# ButtonsLEDs.net
KiCad netlist of a schematic drawn in EAGLE
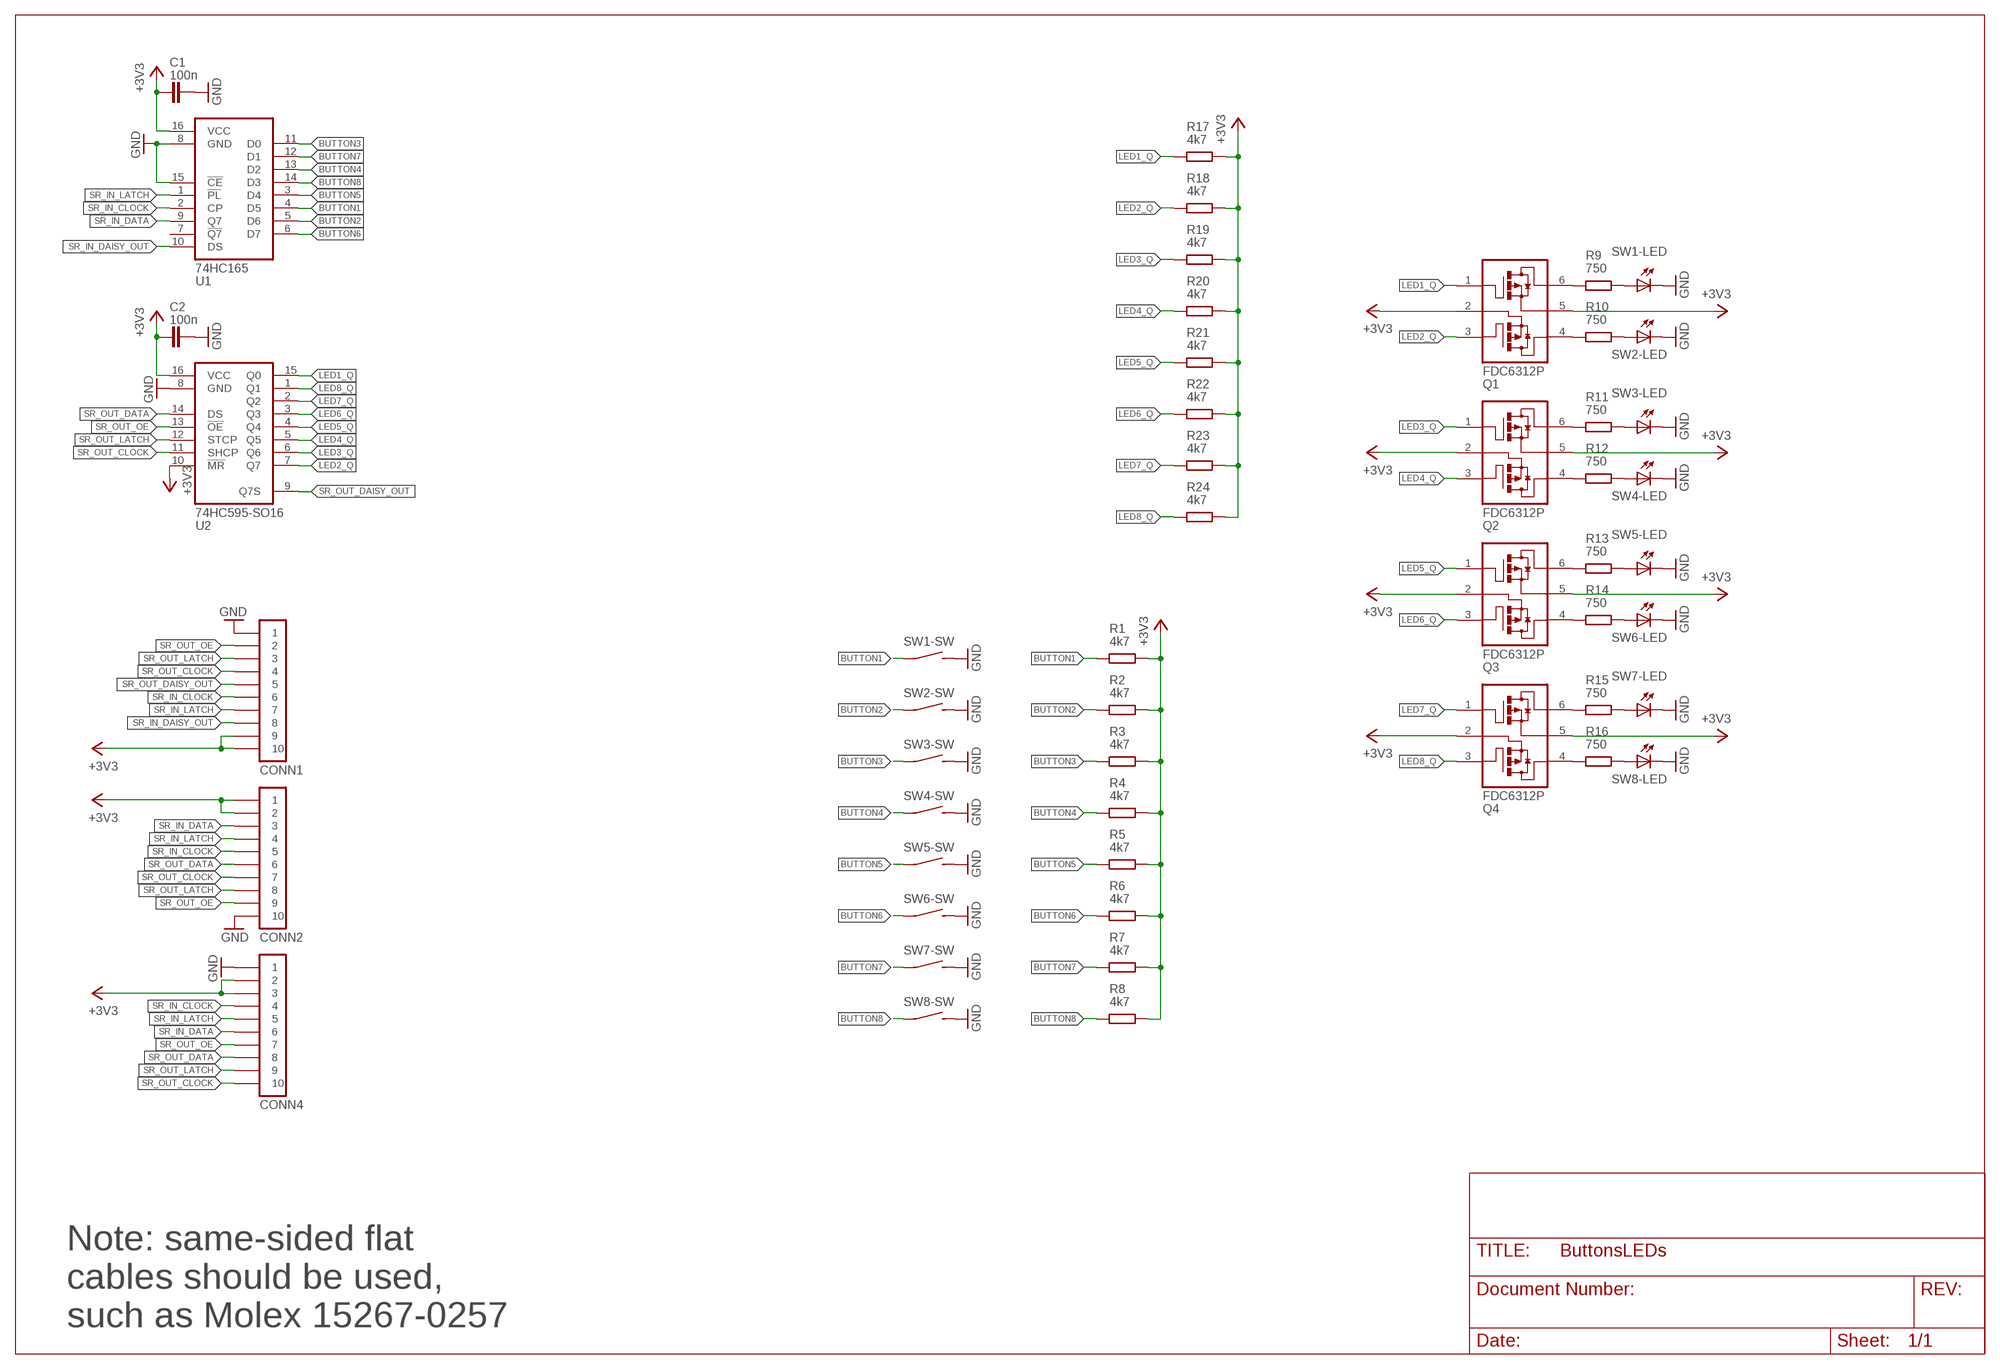
[diagram p0: schematic, sheet 1]

(export (version "E")
  (design (tool "Eeschema 10.0.6"))
  (components
    (comp (ref "C1")
      (value "100n")
      (footprint "eagle-import:C0805")
      (libsource (lib "eagle-import") (part "CAPACITOR-0805"))
    )
    (comp (ref "C2")
      (value "100n")
      (footprint "eagle-import:C0805")
      (libsource (lib "eagle-import") (part "CAPACITOR-0805"))
    )
    (comp (ref "CONN1")
      (value "PINHD-1X10-FFC-1MM-Z")
      (footprint "eagle-import:MOLEX-52271-1079")
      (fields (field (name "MANUFACTURER") "Molex") (field (name "MPN") "52271-1079"))
      (libsource (lib "eagle-import") (part "PINHD-1X10-FFC-1MM-Z"))
    )
    (comp (ref "CONN2")
      (value "PINHD-1X10-FFC-1MM-Z")
      (footprint "eagle-import:MOLEX-52271-1079")
      (fields (field (name "MANUFACTURER") "Molex") (field (name "MPN") "52271-1079"))
      (libsource (lib "eagle-import") (part "PINHD-1X10-FFC-1MM-Z"))
    )
    (comp (ref "CONN4")
      (value "PINHD-1X10-FFC-1MM-Z")
      (footprint "eagle-import:MOLEX-52271-1079")
      (fields (field (name "MANUFACTURER") "Molex") (field (name "MPN") "52271-1079"))
      (libsource (lib "eagle-import") (part "PINHD-1X10-FFC-1MM-Z"))
    )
    (comp (ref "Q1")
      (value "FDC6312P")
      (footprint "eagle-import:SSOT6")
      (fields (field (name "MANUFACTURER") "ON Semiconductor"))
      (libsource (lib "eagle-import") (part "FDC6312P"))
    )
    (comp (ref "Q2")
      (value "FDC6312P")
      (footprint "eagle-import:SSOT6")
      (fields (field (name "MANUFACTURER") "ON Semiconductor"))
      (libsource (lib "eagle-import") (part "FDC6312P"))
    )
    (comp (ref "Q3")
      (value "FDC6312P")
      (footprint "eagle-import:SSOT6")
      (fields (field (name "MANUFACTURER") "ON Semiconductor"))
      (libsource (lib "eagle-import") (part "FDC6312P"))
    )
    (comp (ref "Q4")
      (value "FDC6312P")
      (footprint "eagle-import:SSOT6")
      (fields (field (name "MANUFACTURER") "ON Semiconductor"))
      (libsource (lib "eagle-import") (part "FDC6312P"))
    )
    (comp (ref "R1")
      (value "4k7")
      (footprint "eagle-import:R0805")
      (libsource (lib "eagle-import") (part "RESISTOR-0805"))
    )
    (comp (ref "R2")
      (value "4k7")
      (footprint "eagle-import:R0805")
      (libsource (lib "eagle-import") (part "RESISTOR-0805"))
    )
    (comp (ref "R3")
      (value "4k7")
      (footprint "eagle-import:R0805")
      (libsource (lib "eagle-import") (part "RESISTOR-0805"))
    )
    (comp (ref "R4")
      (value "4k7")
      (footprint "eagle-import:R0805")
      (libsource (lib "eagle-import") (part "RESISTOR-0805"))
    )
    (comp (ref "R5")
      (value "4k7")
      (footprint "eagle-import:R0805")
      (libsource (lib "eagle-import") (part "RESISTOR-0805"))
    )
    (comp (ref "R6")
      (value "4k7")
      (footprint "eagle-import:R0805")
      (libsource (lib "eagle-import") (part "RESISTOR-0805"))
    )
    (comp (ref "R7")
      (value "4k7")
      (footprint "eagle-import:R0805")
      (libsource (lib "eagle-import") (part "RESISTOR-0805"))
    )
    (comp (ref "R8")
      (value "4k7")
      (footprint "eagle-import:R0805")
      (libsource (lib "eagle-import") (part "RESISTOR-0805"))
    )
    (comp (ref "R9")
      (value "750")
      (footprint "eagle-import:R0805")
      (libsource (lib "eagle-import") (part "RESISTOR-0805"))
    )
    (comp (ref "R10")
      (value "750")
      (footprint "eagle-import:R0805")
      (libsource (lib "eagle-import") (part "RESISTOR-0805"))
    )
    (comp (ref "R11")
      (value "750")
      (footprint "eagle-import:R0805")
      (libsource (lib "eagle-import") (part "RESISTOR-0805"))
    )
    (comp (ref "R12")
      (value "750")
      (footprint "eagle-import:R0805")
      (libsource (lib "eagle-import") (part "RESISTOR-0805"))
    )
    (comp (ref "R13")
      (value "750")
      (footprint "eagle-import:R0805")
      (libsource (lib "eagle-import") (part "RESISTOR-0805"))
    )
    (comp (ref "R14")
      (value "750")
      (footprint "eagle-import:R0805")
      (libsource (lib "eagle-import") (part "RESISTOR-0805"))
    )
    (comp (ref "R15")
      (value "750")
      (footprint "eagle-import:R0805")
      (libsource (lib "eagle-import") (part "RESISTOR-0805"))
    )
    (comp (ref "R16")
      (value "750")
      (footprint "eagle-import:R0805")
      (libsource (lib "eagle-import") (part "RESISTOR-0805"))
    )
    (comp (ref "R17")
      (value "4k7")
      (footprint "eagle-import:R0805")
      (libsource (lib "eagle-import") (part "RESISTOR-0805"))
    )
    (comp (ref "R18")
      (value "4k7")
      (footprint "eagle-import:R0805")
      (libsource (lib "eagle-import") (part "RESISTOR-0805"))
    )
    (comp (ref "R19")
      (value "4k7")
      (footprint "eagle-import:R0805")
      (libsource (lib "eagle-import") (part "RESISTOR-0805"))
    )
    (comp (ref "R20")
      (value "4k7")
      (footprint "eagle-import:R0805")
      (libsource (lib "eagle-import") (part "RESISTOR-0805"))
    )
    (comp (ref "R21")
      (value "4k7")
      (footprint "eagle-import:R0805")
      (libsource (lib "eagle-import") (part "RESISTOR-0805"))
    )
    (comp (ref "R22")
      (value "4k7")
      (footprint "eagle-import:R0805")
      (libsource (lib "eagle-import") (part "RESISTOR-0805"))
    )
    (comp (ref "R23")
      (value "4k7")
      (footprint "eagle-import:R0805")
      (libsource (lib "eagle-import") (part "RESISTOR-0805"))
    )
    (comp (ref "R24")
      (value "4k7")
      (footprint "eagle-import:R0805")
      (libsource (lib "eagle-import") (part "RESISTOR-0805"))
    )
    (comp (ref "SW1")
      (value "OMRON-B3W-9")
      (footprint "eagle-import:OMRON-B3W-9")
      (libsource (lib "eagle-import") (part "OMRON-B3W-9"))
    )
    (comp (ref "SW2")
      (value "OMRON-B3W-9")
      (footprint "eagle-import:OMRON-B3W-9")
      (libsource (lib "eagle-import") (part "OMRON-B3W-9"))
    )
    (comp (ref "SW3")
      (value "OMRON-B3W-9")
      (footprint "eagle-import:OMRON-B3W-9")
      (libsource (lib "eagle-import") (part "OMRON-B3W-9"))
    )
    (comp (ref "SW4")
      (value "OMRON-B3W-9")
      (footprint "eagle-import:OMRON-B3W-9")
      (libsource (lib "eagle-import") (part "OMRON-B3W-9"))
    )
    (comp (ref "SW5")
      (value "OMRON-B3W-9")
      (footprint "eagle-import:OMRON-B3W-9")
      (libsource (lib "eagle-import") (part "OMRON-B3W-9"))
    )
    (comp (ref "SW6")
      (value "OMRON-B3W-9")
      (footprint "eagle-import:OMRON-B3W-9")
      (libsource (lib "eagle-import") (part "OMRON-B3W-9"))
    )
    (comp (ref "SW7")
      (value "OMRON-B3W-9")
      (footprint "eagle-import:OMRON-B3W-9")
      (libsource (lib "eagle-import") (part "OMRON-B3W-9"))
    )
    (comp (ref "SW8")
      (value "OMRON-B3W-9")
      (footprint "eagle-import:OMRON-B3W-9")
      (libsource (lib "eagle-import") (part "OMRON-B3W-9"))
    )
    (comp (ref "U1")
      (value "74HC165")
      (footprint "eagle-import:SO16")
      (fields (field (name "MANUFACTURER") "Nexperia") (field (name "MPN") "74HC165D"))
      (libsource (lib "eagle-import") (part "74165HC"))
    )
    (comp (ref "U2")
      (value "74HC595-SO16")
      (footprint "eagle-import:SO16")
      (fields (field (name "MANUFACTURER") "Nexperia") (field (name "MPN") "74HC595D"))
      (libsource (lib "eagle-import") (part "74595-SO16HC"))
    )
  )
  (nets
    (net (code "1") (name "+3V3") (class "Default")
      (node (ref "C1") (pin "1") (pinfunction "1_1") (pintype "passive"))
      (node (ref "C2") (pin "1") (pinfunction "1_1") (pintype "passive"))
      (node (ref "CONN1") (pin "10") (pinfunction "10_10") (pintype "passive"))
      (node (ref "CONN1") (pin "9") (pinfunction "9_9") (pintype "passive"))
      (node (ref "CONN2") (pin "1") (pinfunction "1_1") (pintype "passive"))
      (node (ref "CONN2") (pin "2") (pinfunction "2_2") (pintype "passive"))
      (node (ref "CONN4") (pin "2") (pinfunction "2_2") (pintype "passive"))
      (node (ref "CONN4") (pin "3") (pinfunction "3_3") (pintype "passive"))
      (node (ref "Q1") (pin "2") (pinfunction "S2_2") (pintype "bidirectional"))
      (node (ref "Q1") (pin "5") (pinfunction "S1_5") (pintype "bidirectional"))
      (node (ref "Q2") (pin "2") (pinfunction "S2_2") (pintype "bidirectional"))
      (node (ref "Q2") (pin "5") (pinfunction "S1_5") (pintype "bidirectional"))
      (node (ref "Q3") (pin "2") (pinfunction "S2_2") (pintype "bidirectional"))
      (node (ref "Q3") (pin "5") (pinfunction "S1_5") (pintype "bidirectional"))
      (node (ref "Q4") (pin "2") (pinfunction "S2_2") (pintype "bidirectional"))
      (node (ref "Q4") (pin "5") (pinfunction "S1_5") (pintype "bidirectional"))
      (node (ref "R1") (pin "2") (pinfunction "2_2") (pintype "passive"))
      (node (ref "R17") (pin "2") (pinfunction "2_2") (pintype "passive"))
      (node (ref "R18") (pin "2") (pinfunction "2_2") (pintype "passive"))
      (node (ref "R19") (pin "2") (pinfunction "2_2") (pintype "passive"))
      (node (ref "R2") (pin "2") (pinfunction "2_2") (pintype "passive"))
      (node (ref "R20") (pin "2") (pinfunction "2_2") (pintype "passive"))
      (node (ref "R21") (pin "2") (pinfunction "2_2") (pintype "passive"))
      (node (ref "R22") (pin "2") (pinfunction "2_2") (pintype "passive"))
      (node (ref "R23") (pin "2") (pinfunction "2_2") (pintype "passive"))
      (node (ref "R24") (pin "2") (pinfunction "2_2") (pintype "passive"))
      (node (ref "R3") (pin "2") (pinfunction "2_2") (pintype "passive"))
      (node (ref "R4") (pin "2") (pinfunction "2_2") (pintype "passive"))
      (node (ref "R5") (pin "2") (pinfunction "2_2") (pintype "passive"))
      (node (ref "R6") (pin "2") (pinfunction "2_2") (pintype "passive"))
      (node (ref "R7") (pin "2") (pinfunction "2_2") (pintype "passive"))
      (node (ref "R8") (pin "2") (pinfunction "2_2") (pintype "passive"))
      (node (ref "U1") (pin "16") (pinfunction "VCC_16") (pintype "power_in"))
      (node (ref "U2") (pin "10") (pinfunction "~{MR}_10") (pintype "input"))
      (node (ref "U2") (pin "16") (pinfunction "VCC_16") (pintype "passive"))
    )
    (net (code "2") (name "BUTTON1") (class "Default")
      (node (ref "R1") (pin "1") (pinfunction "1_1") (pintype "passive"))
      (node (ref "SW1") (pin "1") (pinfunction "1_1") (pintype "passive"))
      (node (ref "U1") (pin "4") (pinfunction "D5_4") (pintype "input"))
    )
    (net (code "3") (name "BUTTON2") (class "Default")
      (node (ref "R2") (pin "1") (pinfunction "1_1") (pintype "passive"))
      (node (ref "SW2") (pin "1") (pinfunction "1_1") (pintype "passive"))
      (node (ref "U1") (pin "5") (pinfunction "D6_5") (pintype "input"))
    )
    (net (code "4") (name "BUTTON3") (class "Default")
      (node (ref "R3") (pin "1") (pinfunction "1_1") (pintype "passive"))
      (node (ref "SW3") (pin "1") (pinfunction "1_1") (pintype "passive"))
      (node (ref "U1") (pin "11") (pinfunction "D0_11") (pintype "input"))
    )
    (net (code "5") (name "BUTTON4") (class "Default")
      (node (ref "R4") (pin "1") (pinfunction "1_1") (pintype "passive"))
      (node (ref "SW4") (pin "1") (pinfunction "1_1") (pintype "passive"))
      (node (ref "U1") (pin "13") (pinfunction "D2_13") (pintype "input"))
    )
    (net (code "6") (name "BUTTON5") (class "Default")
      (node (ref "R5") (pin "1") (pinfunction "1_1") (pintype "passive"))
      (node (ref "SW5") (pin "1") (pinfunction "1_1") (pintype "passive"))
      (node (ref "U1") (pin "3") (pinfunction "D4_3") (pintype "input"))
    )
    (net (code "7") (name "BUTTON6") (class "Default")
      (node (ref "R6") (pin "1") (pinfunction "1_1") (pintype "passive"))
      (node (ref "SW6") (pin "1") (pinfunction "1_1") (pintype "passive"))
      (node (ref "U1") (pin "6") (pinfunction "D7_6") (pintype "input"))
    )
    (net (code "8") (name "BUTTON7") (class "Default")
      (node (ref "R7") (pin "1") (pinfunction "1_1") (pintype "passive"))
      (node (ref "SW7") (pin "1") (pinfunction "1_1") (pintype "passive"))
      (node (ref "U1") (pin "12") (pinfunction "D1_12") (pintype "input"))
    )
    (net (code "9") (name "BUTTON8") (class "Default")
      (node (ref "R8") (pin "1") (pinfunction "1_1") (pintype "passive"))
      (node (ref "SW8") (pin "1") (pinfunction "1_1") (pintype "passive"))
      (node (ref "U1") (pin "14") (pinfunction "D3_14") (pintype "input"))
    )
    (net (code "10") (name "GND") (class "Default")
      (node (ref "C1") (pin "2") (pinfunction "2_2") (pintype "passive"))
      (node (ref "C2") (pin "2") (pinfunction "2_2") (pintype "passive"))
      (node (ref "CONN1") (pin "1") (pinfunction "1_1") (pintype "passive"))
      (node (ref "CONN2") (pin "10") (pinfunction "10_10") (pintype "passive"))
      (node (ref "CONN4") (pin "1") (pinfunction "1_1") (pintype "passive"))
      (node (ref "SW1") (pin "3") (pinfunction "2_3") (pintype "passive"))
      (node (ref "SW1") (pin "6-C") (pinfunction "C_6-C") (pintype "passive"))
      (node (ref "SW2") (pin "3") (pinfunction "2_3") (pintype "passive"))
      (node (ref "SW2") (pin "6-C") (pinfunction "C_6-C") (pintype "passive"))
      (node (ref "SW3") (pin "3") (pinfunction "2_3") (pintype "passive"))
      (node (ref "SW3") (pin "6-C") (pinfunction "C_6-C") (pintype "passive"))
      (node (ref "SW4") (pin "3") (pinfunction "2_3") (pintype "passive"))
      (node (ref "SW4") (pin "6-C") (pinfunction "C_6-C") (pintype "passive"))
      (node (ref "SW5") (pin "3") (pinfunction "2_3") (pintype "passive"))
      (node (ref "SW5") (pin "6-C") (pinfunction "C_6-C") (pintype "passive"))
      (node (ref "SW6") (pin "3") (pinfunction "2_3") (pintype "passive"))
      (node (ref "SW6") (pin "6-C") (pinfunction "C_6-C") (pintype "passive"))
      (node (ref "SW7") (pin "3") (pinfunction "2_3") (pintype "passive"))
      (node (ref "SW7") (pin "6-C") (pinfunction "C_6-C") (pintype "passive"))
      (node (ref "SW8") (pin "3") (pinfunction "2_3") (pintype "passive"))
      (node (ref "SW8") (pin "6-C") (pinfunction "C_6-C") (pintype "passive"))
      (node (ref "U1") (pin "15") (pinfunction "~{CE}_15") (pintype "input"))
      (node (ref "U1") (pin "8") (pinfunction "GND_8") (pintype "power_in"))
      (node (ref "U2") (pin "8") (pinfunction "GND_8") (pintype "passive"))
    )
    (net (code "11") (name "LED1_Q") (class "Default")
      (node (ref "Q1") (pin "1") (pinfunction "G1_1") (pintype "bidirectional"))
      (node (ref "R17") (pin "1") (pinfunction "1_1") (pintype "passive"))
      (node (ref "U2") (pin "15") (pinfunction "Q0_15") (pintype "passive"))
    )
    (net (code "12") (name "LED2_Q") (class "Default")
      (node (ref "Q1") (pin "3") (pinfunction "G2_3") (pintype "bidirectional"))
      (node (ref "R18") (pin "1") (pinfunction "1_1") (pintype "passive"))
      (node (ref "U2") (pin "7") (pinfunction "Q7_7") (pintype "passive"))
    )
    (net (code "13") (name "LED3_Q") (class "Default")
      (node (ref "Q2") (pin "1") (pinfunction "G1_1") (pintype "bidirectional"))
      (node (ref "R19") (pin "1") (pinfunction "1_1") (pintype "passive"))
      (node (ref "U2") (pin "6") (pinfunction "Q6_6") (pintype "passive"))
    )
    (net (code "14") (name "LED4_Q") (class "Default")
      (node (ref "Q2") (pin "3") (pinfunction "G2_3") (pintype "bidirectional"))
      (node (ref "R20") (pin "1") (pinfunction "1_1") (pintype "passive"))
      (node (ref "U2") (pin "5") (pinfunction "Q5_5") (pintype "passive"))
    )
    (net (code "15") (name "LED5_Q") (class "Default")
      (node (ref "Q3") (pin "1") (pinfunction "G1_1") (pintype "bidirectional"))
      (node (ref "R21") (pin "1") (pinfunction "1_1") (pintype "passive"))
      (node (ref "U2") (pin "4") (pinfunction "Q4_4") (pintype "passive"))
    )
    (net (code "16") (name "LED6_Q") (class "Default")
      (node (ref "Q3") (pin "3") (pinfunction "G2_3") (pintype "bidirectional"))
      (node (ref "R22") (pin "1") (pinfunction "1_1") (pintype "passive"))
      (node (ref "U2") (pin "3") (pinfunction "Q3_3") (pintype "passive"))
    )
    (net (code "17") (name "LED7_Q") (class "Default")
      (node (ref "Q4") (pin "1") (pinfunction "G1_1") (pintype "bidirectional"))
      (node (ref "R23") (pin "1") (pinfunction "1_1") (pintype "passive"))
      (node (ref "U2") (pin "2") (pinfunction "Q2_2") (pintype "passive"))
    )
    (net (code "18") (name "LED8_Q") (class "Default")
      (node (ref "Q4") (pin "3") (pinfunction "G2_3") (pintype "bidirectional"))
      (node (ref "R24") (pin "1") (pinfunction "1_1") (pintype "passive"))
      (node (ref "U2") (pin "1") (pinfunction "Q1_1") (pintype "passive"))
    )
    (net (code "19") (name "Net-(Q1-D1)") (class "Default")
      (node (ref "Q1") (pin "6") (pinfunction "D1_6") (pintype "bidirectional"))
      (node (ref "R9") (pin "1") (pinfunction "1_1") (pintype "passive"))
    )
    (net (code "20") (name "Net-(Q1-D2)") (class "Default")
      (node (ref "Q1") (pin "4") (pinfunction "D2_4") (pintype "bidirectional"))
      (node (ref "R10") (pin "1") (pinfunction "1_1") (pintype "passive"))
    )
    (net (code "21") (name "Net-(Q2-D1)") (class "Default")
      (node (ref "Q2") (pin "6") (pinfunction "D1_6") (pintype "bidirectional"))
      (node (ref "R11") (pin "1") (pinfunction "1_1") (pintype "passive"))
    )
    (net (code "22") (name "Net-(Q2-D2)") (class "Default")
      (node (ref "Q2") (pin "4") (pinfunction "D2_4") (pintype "bidirectional"))
      (node (ref "R12") (pin "1") (pinfunction "1_1") (pintype "passive"))
    )
    (net (code "23") (name "Net-(Q3-D1)") (class "Default")
      (node (ref "Q3") (pin "6") (pinfunction "D1_6") (pintype "bidirectional"))
      (node (ref "R13") (pin "1") (pinfunction "1_1") (pintype "passive"))
    )
    (net (code "24") (name "Net-(Q3-D2)") (class "Default")
      (node (ref "Q3") (pin "4") (pinfunction "D2_4") (pintype "bidirectional"))
      (node (ref "R14") (pin "1") (pinfunction "1_1") (pintype "passive"))
    )
    (net (code "25") (name "Net-(Q4-D1)") (class "Default")
      (node (ref "Q4") (pin "6") (pinfunction "D1_6") (pintype "bidirectional"))
      (node (ref "R15") (pin "1") (pinfunction "1_1") (pintype "passive"))
    )
    (net (code "26") (name "Net-(Q4-D2)") (class "Default")
      (node (ref "Q4") (pin "4") (pinfunction "D2_4") (pintype "bidirectional"))
      (node (ref "R16") (pin "1") (pinfunction "1_1") (pintype "passive"))
    )
    (net (code "27") (name "Net-(SW1A-A)") (class "Default")
      (node (ref "R9") (pin "2") (pinfunction "2_2") (pintype "passive"))
      (node (ref "SW1") (pin "6-A") (pinfunction "A_6-A") (pintype "passive"))
    )
    (net (code "28") (name "Net-(SW2A-A)") (class "Default")
      (node (ref "R10") (pin "2") (pinfunction "2_2") (pintype "passive"))
      (node (ref "SW2") (pin "6-A") (pinfunction "A_6-A") (pintype "passive"))
    )
    (net (code "29") (name "Net-(SW3A-A)") (class "Default")
      (node (ref "R11") (pin "2") (pinfunction "2_2") (pintype "passive"))
      (node (ref "SW3") (pin "6-A") (pinfunction "A_6-A") (pintype "passive"))
    )
    (net (code "30") (name "Net-(SW4A-A)") (class "Default")
      (node (ref "R12") (pin "2") (pinfunction "2_2") (pintype "passive"))
      (node (ref "SW4") (pin "6-A") (pinfunction "A_6-A") (pintype "passive"))
    )
    (net (code "31") (name "Net-(SW5A-A)") (class "Default")
      (node (ref "R13") (pin "2") (pinfunction "2_2") (pintype "passive"))
      (node (ref "SW5") (pin "6-A") (pinfunction "A_6-A") (pintype "passive"))
    )
    (net (code "32") (name "Net-(SW6A-A)") (class "Default")
      (node (ref "R14") (pin "2") (pinfunction "2_2") (pintype "passive"))
      (node (ref "SW6") (pin "6-A") (pinfunction "A_6-A") (pintype "passive"))
    )
    (net (code "33") (name "Net-(SW7A-A)") (class "Default")
      (node (ref "R15") (pin "2") (pinfunction "2_2") (pintype "passive"))
      (node (ref "SW7") (pin "6-A") (pinfunction "A_6-A") (pintype "passive"))
    )
    (net (code "34") (name "Net-(SW8A-A)") (class "Default")
      (node (ref "R16") (pin "2") (pinfunction "2_2") (pintype "passive"))
      (node (ref "SW8") (pin "6-A") (pinfunction "A_6-A") (pintype "passive"))
    )
    (net (code "35") (name "SR_IN_CLOCK") (class "Default")
      (node (ref "CONN1") (pin "6") (pinfunction "6_6") (pintype "passive"))
      (node (ref "CONN2") (pin "5") (pinfunction "5_5") (pintype "passive"))
      (node (ref "CONN4") (pin "4") (pinfunction "4_4") (pintype "passive"))
      (node (ref "U1") (pin "2") (pinfunction "CP_2") (pintype "bidirectional"))
    )
    (net (code "36") (name "SR_IN_DAISY_OUT") (class "Default")
      (node (ref "CONN1") (pin "8") (pinfunction "8_8") (pintype "passive"))
      (node (ref "U1") (pin "10") (pinfunction "DS_10") (pintype "bidirectional"))
    )
    (net (code "37") (name "SR_IN_DATA") (class "Default")
      (node (ref "CONN2") (pin "3") (pinfunction "3_3") (pintype "passive"))
      (node (ref "CONN4") (pin "6") (pinfunction "6_6") (pintype "passive"))
      (node (ref "U1") (pin "9") (pinfunction "Q7_9") (pintype "output"))
    )
    (net (code "38") (name "SR_IN_LATCH") (class "Default")
      (node (ref "CONN1") (pin "7") (pinfunction "7_7") (pintype "passive"))
      (node (ref "CONN2") (pin "4") (pinfunction "4_4") (pintype "passive"))
      (node (ref "CONN4") (pin "5") (pinfunction "5_5") (pintype "passive"))
      (node (ref "U1") (pin "1") (pinfunction "~{PL}_1") (pintype "input"))
    )
    (net (code "39") (name "SR_OUT_CLOCK") (class "Default")
      (node (ref "CONN1") (pin "4") (pinfunction "4_4") (pintype "passive"))
      (node (ref "CONN2") (pin "7") (pinfunction "7_7") (pintype "passive"))
      (node (ref "CONN4") (pin "10") (pinfunction "10_10") (pintype "passive"))
      (node (ref "U2") (pin "11") (pinfunction "SHCP_11") (pintype "input"))
    )
    (net (code "40") (name "SR_OUT_DAISY_OUT") (class "Default")
      (node (ref "CONN1") (pin "5") (pinfunction "5_5") (pintype "passive"))
      (node (ref "U2") (pin "9") (pinfunction "Q7S_9") (pintype "output"))
    )
    (net (code "41") (name "SR_OUT_DATA") (class "Default")
      (node (ref "CONN2") (pin "6") (pinfunction "6_6") (pintype "passive"))
      (node (ref "CONN4") (pin "8") (pinfunction "8_8") (pintype "passive"))
      (node (ref "U2") (pin "14") (pinfunction "DS_14") (pintype "input"))
    )
    (net (code "42") (name "SR_OUT_LATCH") (class "Default")
      (node (ref "CONN1") (pin "3") (pinfunction "3_3") (pintype "passive"))
      (node (ref "CONN2") (pin "8") (pinfunction "8_8") (pintype "passive"))
      (node (ref "CONN4") (pin "9") (pinfunction "9_9") (pintype "passive"))
      (node (ref "U2") (pin "12") (pinfunction "STCP_12") (pintype "input"))
    )
    (net (code "43") (name "SR_OUT_OE") (class "Default")
      (node (ref "CONN1") (pin "2") (pinfunction "2_2") (pintype "passive"))
      (node (ref "CONN2") (pin "9") (pinfunction "9_9") (pintype "passive"))
      (node (ref "CONN4") (pin "7") (pinfunction "7_7") (pintype "passive"))
      (node (ref "U2") (pin "13") (pinfunction "~{OE}_13") (pintype "input"))
    )
    (net (code "44") (name "unconnected-(U1-~{Q7}-Pad7)") (class "Default")
      (node (ref "U1") (pin "7") (pinfunction "~{Q7}_7") (pintype "output"))
    )
  )
)
